# TMotor_Rev0_5_1_Jan30.net
KiCad netlist of a schematic drawn in EAGLE
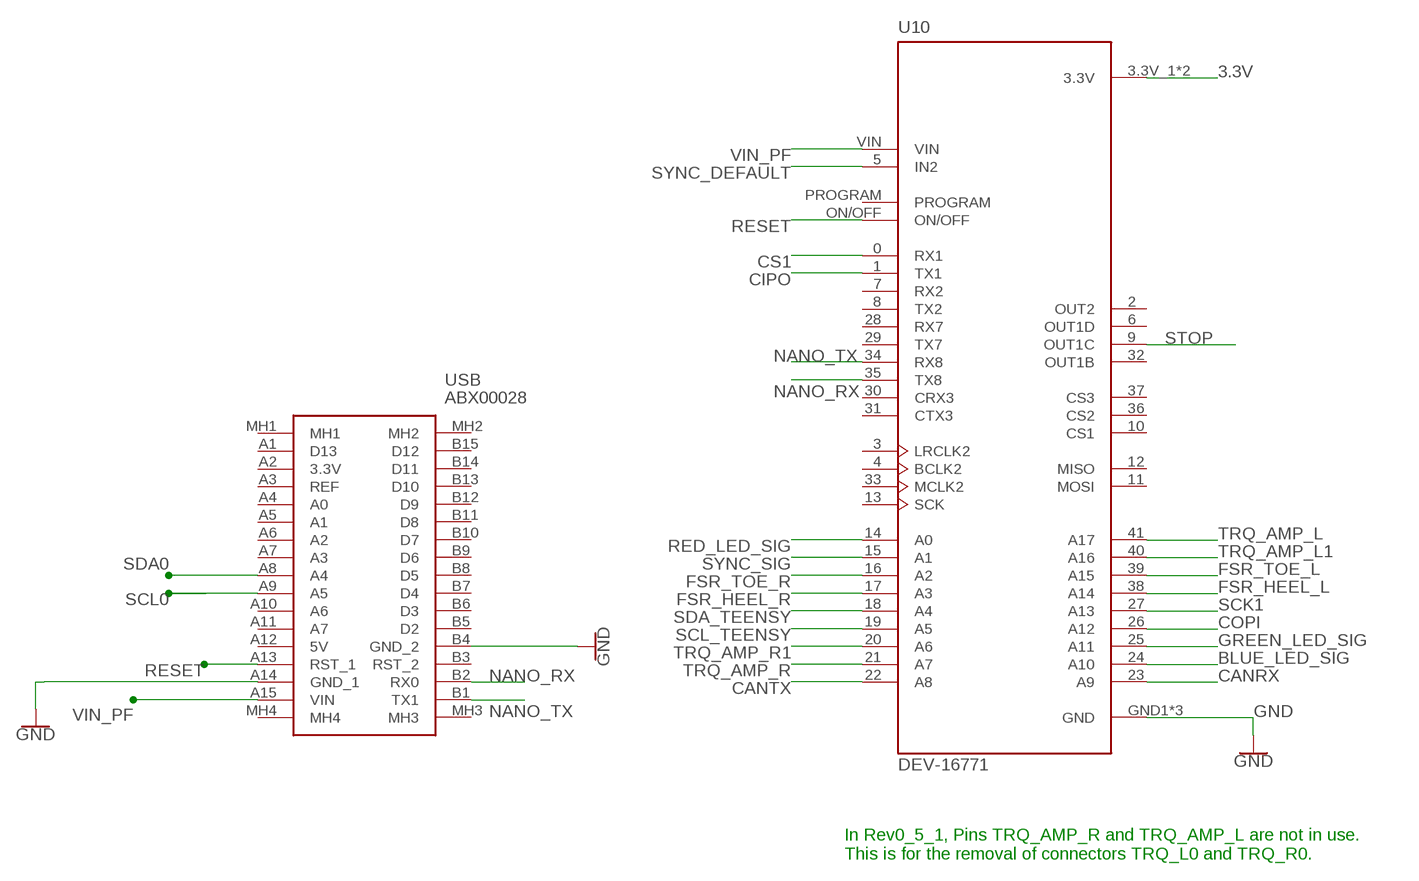
[diagram p0: schematic, sheet 1]
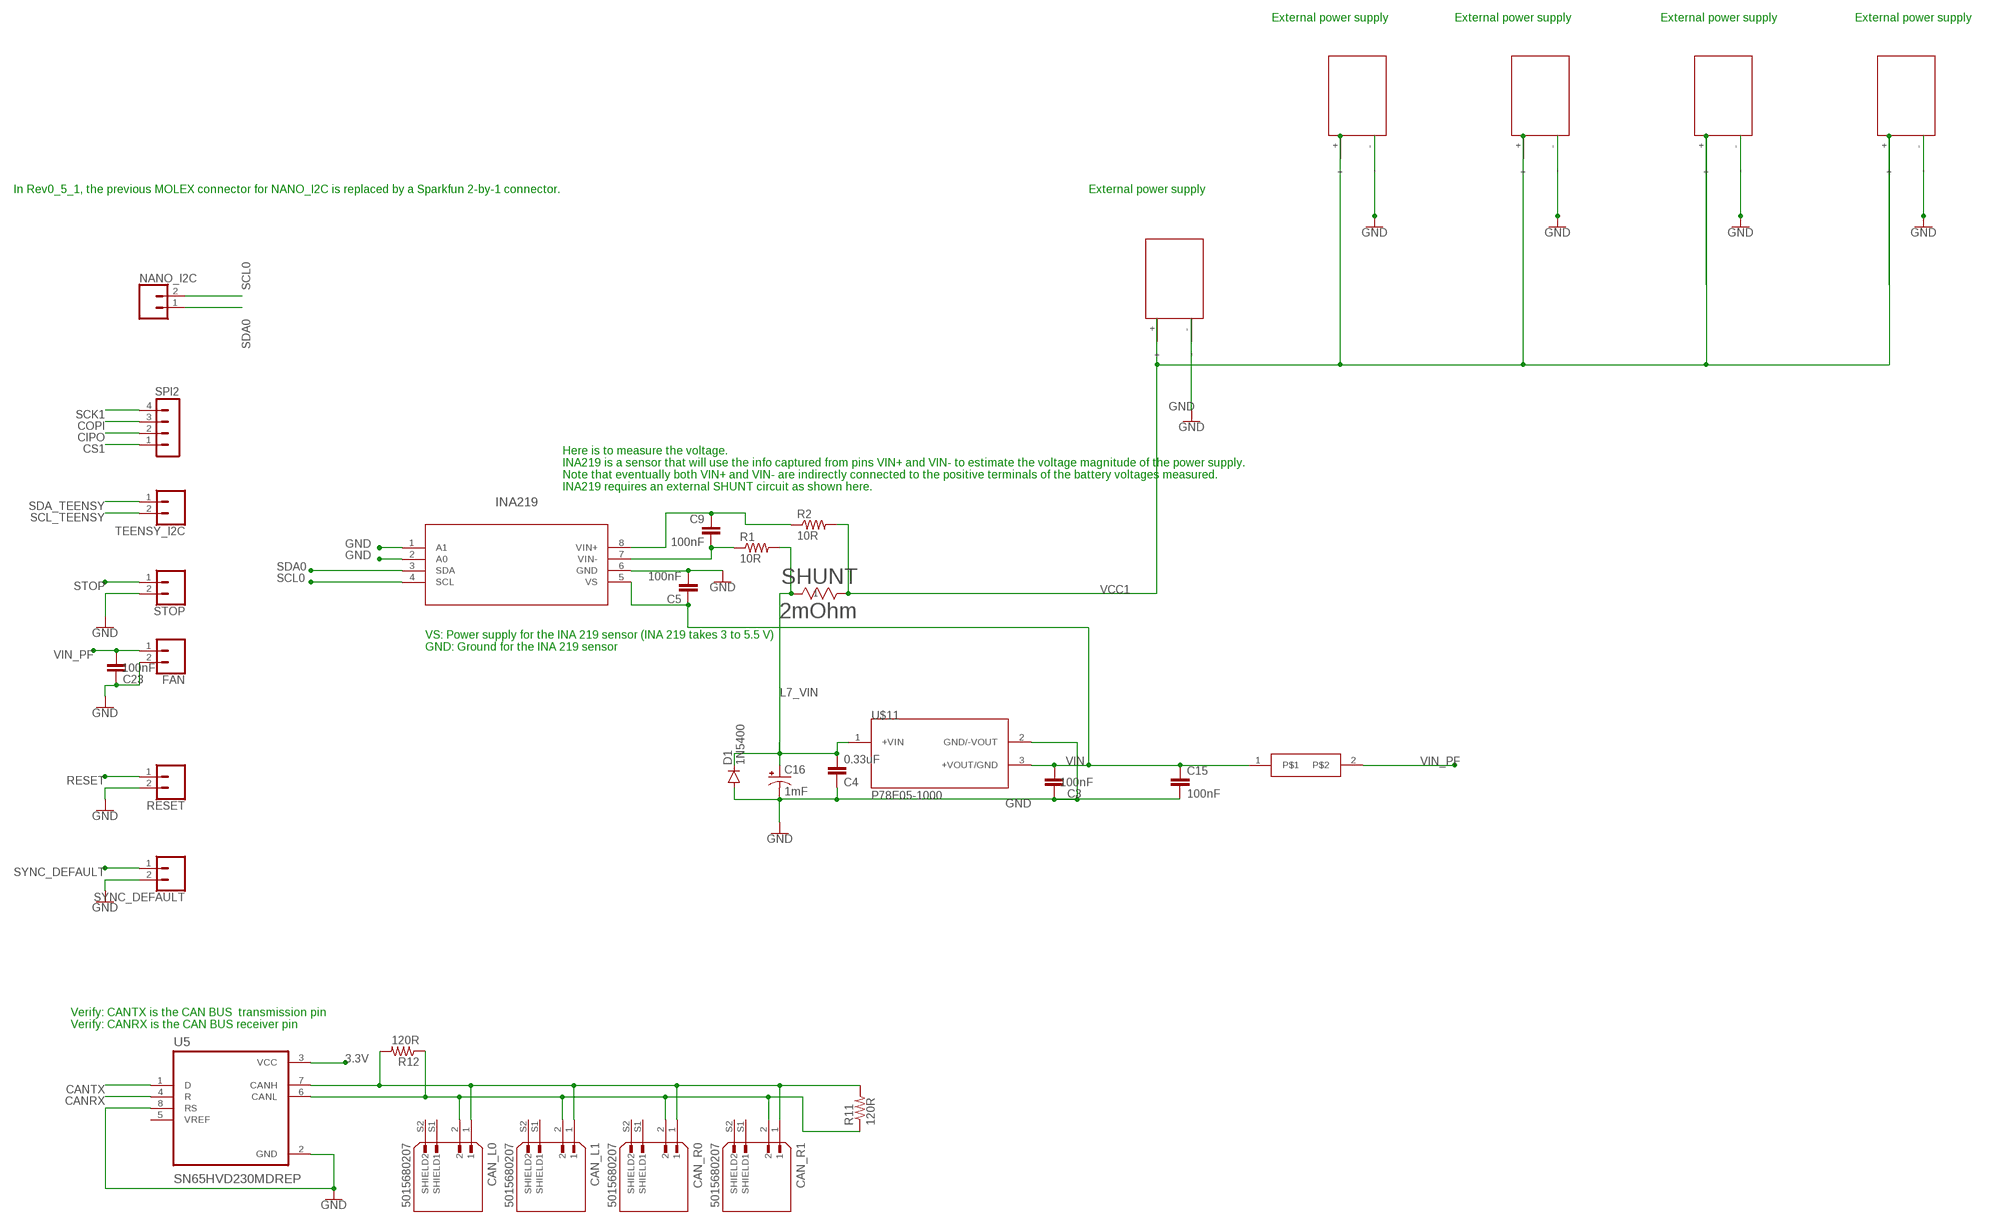
[diagram p1: schematic, sheet 2]
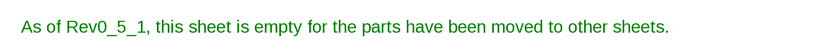
[diagram p2: schematic, sheet 3]
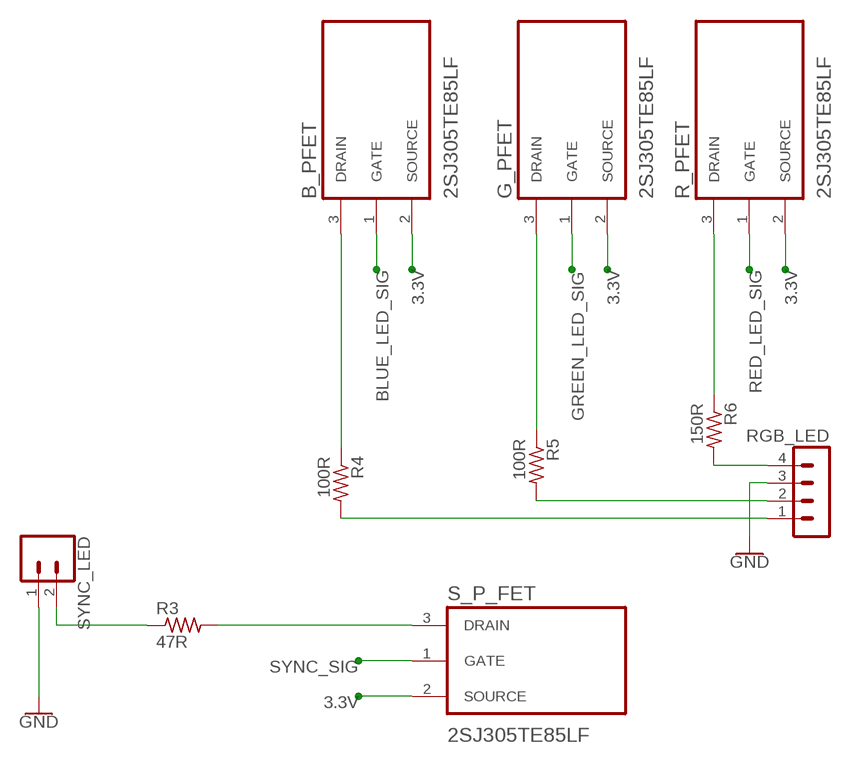
[diagram p3: schematic, sheet 4]
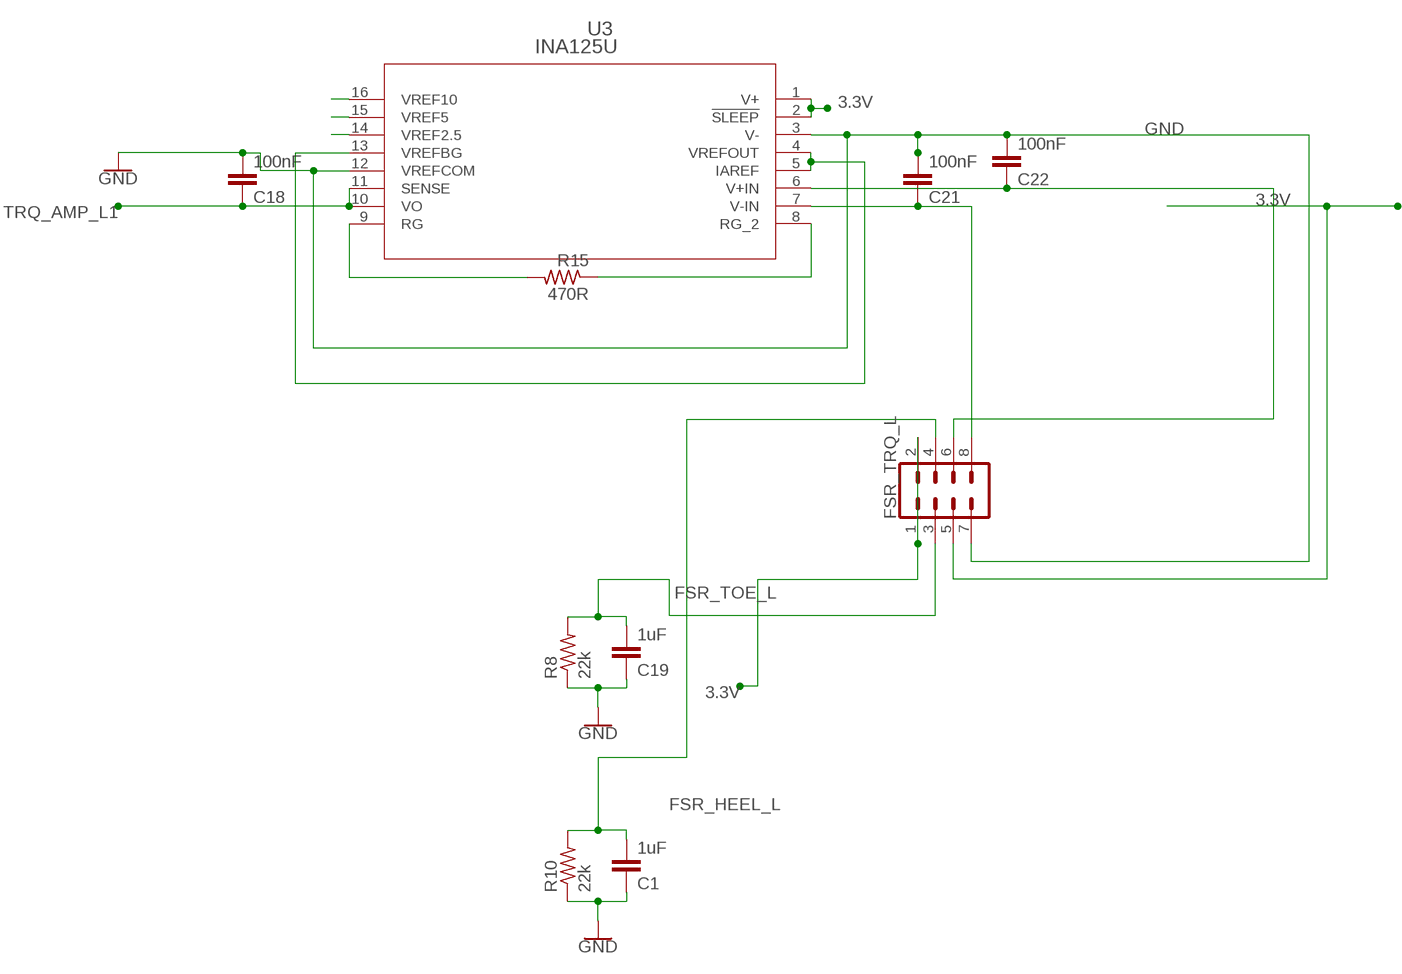
[diagram p4: schematic, sheet 5, part 1 of 2]
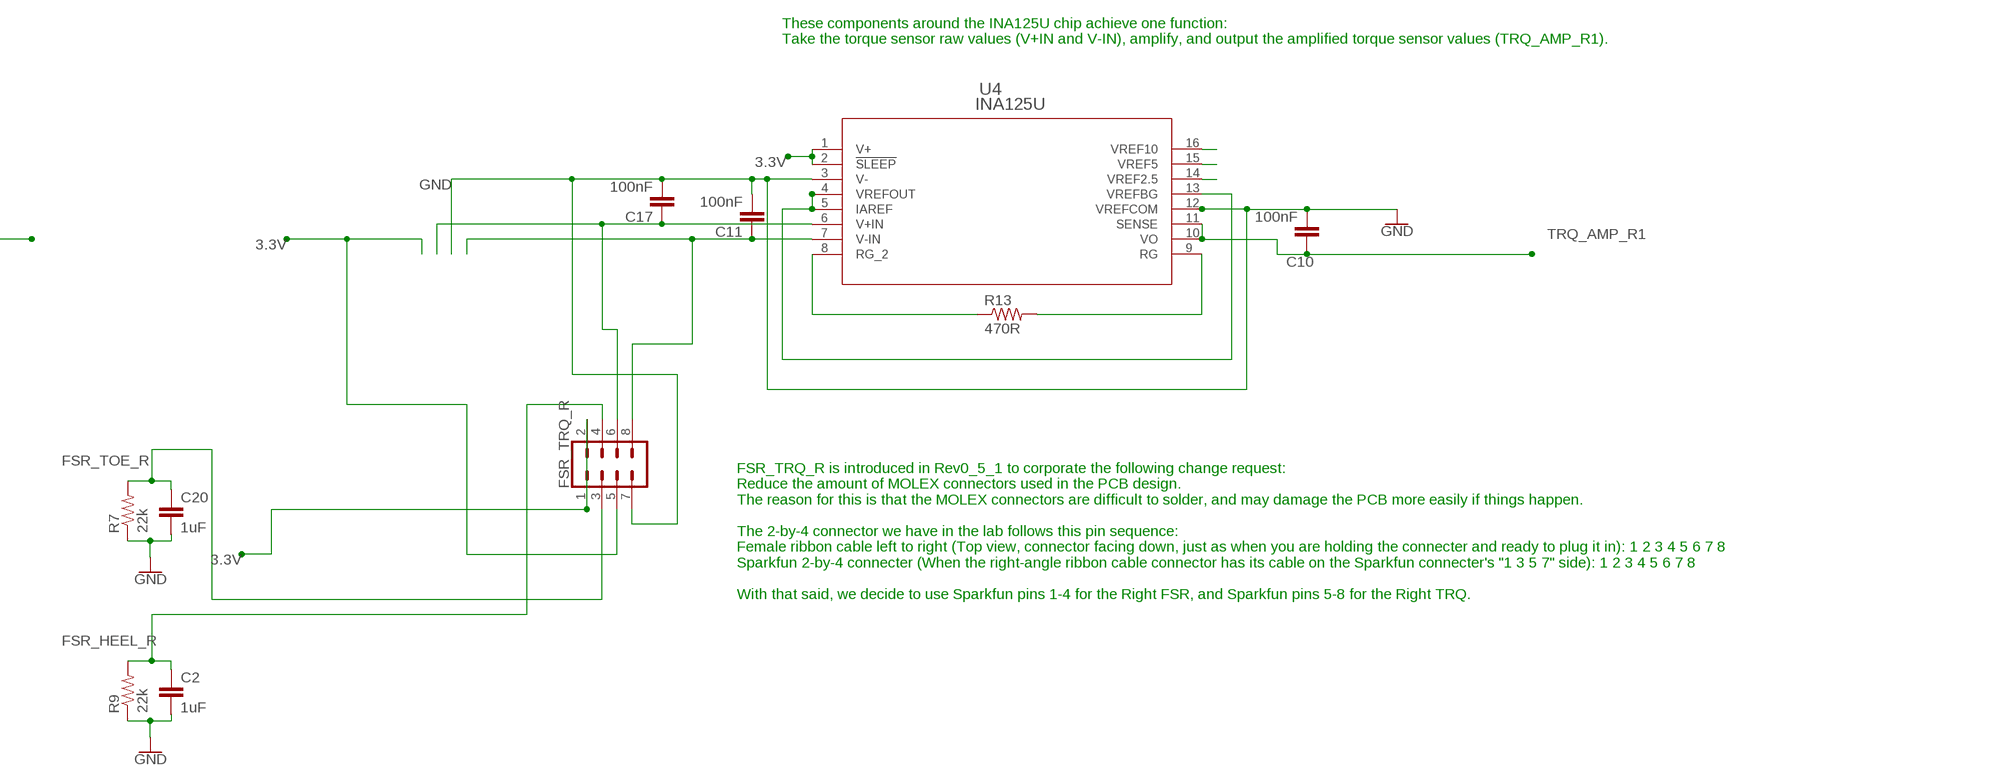
[diagram p5: schematic, sheet 5, part 2 of 2]

(export (version "E")
  (design (tool "Eeschema 10.0.6"))
  (components
    (comp (ref "C1")
      (value "1uF")
      (footprint "eagle-import:C050-024X044")
      (libsource (lib "eagle-import") (part "C-EU050-024X044"))
    )
    (comp (ref "C2")
      (value "1uF")
      (footprint "eagle-import:C050-024X044")
      (libsource (lib "eagle-import") (part "C-EU050-024X044"))
    )
    (comp (ref "C10")
      (value "100nF")
      (footprint "eagle-import:C050-024X044")
      (libsource (lib "eagle-import") (part "C-EU050-024X044"))
    )
    (comp (ref "C11")
      (value "100nF")
      (footprint "eagle-import:C050-024X044")
      (libsource (lib "eagle-import") (part "C-EU050-024X044"))
    )
    (comp (ref "C17")
      (value "100nF")
      (footprint "eagle-import:C050-024X044")
      (libsource (lib "eagle-import") (part "C-EU050-024X044"))
    )
    (comp (ref "C18")
      (value "100nF")
      (footprint "eagle-import:C050-024X044")
      (libsource (lib "eagle-import") (part "C-EU050-024X044"))
    )
    (comp (ref "C19")
      (value "1uF")
      (footprint "eagle-import:C050-024X044")
      (libsource (lib "eagle-import") (part "C-EU050-024X044"))
    )
    (comp (ref "C20")
      (value "1uF")
      (footprint "eagle-import:C050-024X044")
      (libsource (lib "eagle-import") (part "C-EU050-024X044"))
    )
    (comp (ref "C21")
      (value "100nF")
      (footprint "eagle-import:C050-024X044")
      (libsource (lib "eagle-import") (part "C-EU050-024X044"))
    )
    (comp (ref "C22")
      (value "100nF")
      (footprint "eagle-import:C050-024X044")
      (libsource (lib "eagle-import") (part "C-EU050-024X044"))
    )
    (comp (ref "FSR_TRQ_L")
      (value "CONN_04X2")
      (footprint "eagle-import:2X4")
      (libsource (lib "eagle-import") (part "CONN_04X2"))
    )
    (comp (ref "FSR_TRQ_R")
      (value "CONN_04X2")
      (footprint "eagle-import:2X4")
      (libsource (lib "eagle-import") (part "CONN_04X2"))
    )
    (comp (ref "R7")
      (value "22k")
      (footprint "eagle-import:0207_10")
      (libsource (lib "eagle-import") (part "resistor_348_R-US_0207/10"))
    )
    (comp (ref "R8")
      (value "22k")
      (footprint "eagle-import:0207_10")
      (libsource (lib "eagle-import") (part "resistor_348_R-US_0207/10"))
    )
    (comp (ref "R9")
      (value "22k")
      (footprint "eagle-import:0207_10")
      (libsource (lib "eagle-import") (part "resistor_348_R-US_0207/10"))
    )
    (comp (ref "R10")
      (value "22k")
      (footprint "eagle-import:0207_10")
      (libsource (lib "eagle-import") (part "resistor_348_R-US_0207/10"))
    )
    (comp (ref "R13")
      (value "470R")
      (footprint "eagle-import:0207_10")
      (libsource (lib "eagle-import") (part "R-US_0207/10"))
    )
    (comp (ref "R15")
      (value "470R")
      (footprint "eagle-import:0207_10")
      (libsource (lib "eagle-import") (part "R-US_0207/10"))
    )
    (comp (ref "U3")
      (value "INA125U")
      (footprint "eagle-import:D16")
      (fields (field (name "GENERIC_PART_NUMBER") "INA125") (field (name "MANUFACTURER") "Texas Instruments"))
      (libsource (lib "eagle-import") (part "INA125U"))
    )
    (comp (ref "U4")
      (value "INA125U")
      (footprint "eagle-import:D16")
      (fields (field (name "GENERIC_PART_NUMBER") "INA125") (field (name "MANUFACTURER") "Texas Instruments"))
      (libsource (lib "eagle-import") (part "INA125U"))
    )
    (comp (ref "B_PFET")
      (value "2SJ305TE85LF")
      (footprint "eagle-import:TRANS_SSM3J325F,LF")
      (fields (field (name "MF") "Toshiba"))
      (libsource (lib "eagle-import") (part "2SJ305TE85LF"))
    )
    (comp (ref "G_PFET")
      (value "2SJ305TE85LF")
      (footprint "eagle-import:TRANS_SSM3J325F,LF")
      (fields (field (name "MF") "Toshiba"))
      (libsource (lib "eagle-import") (part "2SJ305TE85LF"))
    )
    (comp (ref "R3")
      (value "47R")
      (footprint "eagle-import:0207_10")
      (libsource (lib "eagle-import") (part "R-US_0207/10"))
    )
    (comp (ref "R4")
      (value "100R")
      (footprint "eagle-import:0207_10")
      (libsource (lib "eagle-import") (part "R-US_0207/10"))
    )
    (comp (ref "R5")
      (value "100R")
      (footprint "eagle-import:0207_10")
      (libsource (lib "eagle-import") (part "R-US_0207/10"))
    )
    (comp (ref "R6")
      (value "150R")
      (footprint "eagle-import:0207_10")
      (libsource (lib "eagle-import") (part "R-US_0207/10"))
    )
    (comp (ref "RGB_LED")
      (value "MA04-1")
      (footprint "eagle-import:MA04-1")
      (libsource (lib "eagle-import") (part "MA04-1"))
    )
    (comp (ref "R_PFET")
      (value "2SJ305TE85LF")
      (footprint "eagle-import:TRANS_SSM3J325F,LF")
      (fields (field (name "MF") "Toshiba"))
      (libsource (lib "eagle-import") (part "2SJ305TE85LF"))
    )
    (comp (ref "SYNC_LED")
      (value "CONN_02")
      (footprint "eagle-import:1X02")
      (libsource (lib "eagle-import") (part "CONN_02"))
    )
    (comp (ref "S_P_FET")
      (value "2SJ305TE85LF")
      (footprint "eagle-import:TRANS_SSM3J325F,LF")
      (fields (field (name "MF") "Toshiba"))
      (libsource (lib "eagle-import") (part "2SJ305TE85LF"))
    )
    (comp (ref "U10")
      (value "DEV-16771")
      (footprint "eagle-import:MODULE_DEV-16771")
      (fields (field (name "MANUFACTURER") "SparkFun Electronics"))
      (libsource (lib "eagle-import") (part "DEV-16771"))
    )
    (comp (ref "USB")
      (value "ABX00028")
      (footprint "eagle-import:ABX00028")
      (fields (field (name "MOUSER_PART_NUMBER") "782-ABX00028"))
      (libsource (lib "eagle-import") (part "ABX00028"))
    )
    (comp (ref "C3")
      (value "100nF")
      (footprint "eagle-import:C050-024X044")
      (libsource (lib "eagle-import") (part "C-EU050-024X044"))
    )
    (comp (ref "C4")
      (value "0.33uF")
      (footprint "eagle-import:C050-024X044")
      (libsource (lib "eagle-import") (part "C-EU050-024X044"))
    )
    (comp (ref "C5")
      (value "100nF")
      (footprint "eagle-import:C050-024X044")
      (libsource (lib "eagle-import") (part "C-EU050-024X044"))
    )
    (comp (ref "C9")
      (value "100nF")
      (footprint "eagle-import:C050-024X044")
      (libsource (lib "eagle-import") (part "C-EU050-024X044"))
    )
    (comp (ref "C15")
      (value "100nF")
      (footprint "eagle-import:C050-024X044")
      (libsource (lib "eagle-import") (part "C-EU050-024X044"))
    )
    (comp (ref "C16")
      (value "1mF")
      (footprint "eagle-import:E5-10,5")
      (libsource (lib "eagle-import") (part "CPOL-USE5-10.5"))
    )
    (comp (ref "C23")
      (value "100nF")
      (footprint "eagle-import:C050-024X044")
      (libsource (lib "eagle-import") (part "C-EU050-024X044"))
    )
    (comp (ref "CAN_L0")
      (value "5015680207")
      (footprint "eagle-import:MOLEX_5015680207")
      (fields (field (name "MANUFACTURER") "Molex"))
      (libsource (lib "eagle-import") (part "5015680207"))
    )
    (comp (ref "CAN_L1")
      (value "5015680207")
      (footprint "eagle-import:MOLEX_5015680207")
      (fields (field (name "MANUFACTURER") "Molex"))
      (libsource (lib "eagle-import") (part "5015680207"))
    )
    (comp (ref "CAN_R0")
      (value "5015680207")
      (footprint "eagle-import:MOLEX_5015680207")
      (fields (field (name "MANUFACTURER") "Molex"))
      (libsource (lib "eagle-import") (part "5015680207"))
    )
    (comp (ref "CAN_R1")
      (value "5015680207")
      (footprint "eagle-import:MOLEX_5015680207")
      (fields (field (name "MANUFACTURER") "Molex"))
      (libsource (lib "eagle-import") (part "5015680207"))
    )
    (comp (ref "D1")
      (value "1N5400")
      (footprint "eagle-import:DO201-15")
      (libsource (lib "eagle-import") (part "1N5400"))
    )
    (comp (ref "FAN")
      (value "CONN_02")
      (footprint "eagle-import:1X02")
      (libsource (lib "eagle-import") (part "CONN_02"))
    )
    (comp (ref "INA219")
      (value "INA219AIDR")
      (footprint "eagle-import:D8_TEX")
      (libsource (lib "eagle-import") (part "INA219AIDR"))
    )
    (comp (ref "NANO_I2C")
      (value "CONN_02")
      (footprint "eagle-import:1X02")
      (libsource (lib "eagle-import") (part "CONN_02"))
    )
    (comp (ref "R1")
      (value "10R")
      (footprint "eagle-import:0207_10")
      (libsource (lib "eagle-import") (part "R-US_0207/10"))
    )
    (comp (ref "R2")
      (value "10R")
      (footprint "eagle-import:0207_10")
      (libsource (lib "eagle-import") (part "R-US_0207/10"))
    )
    (comp (ref "R11")
      (value "120R")
      (footprint "eagle-import:0207_10")
      (libsource (lib "eagle-import") (part "R-US_0207/10"))
    )
    (comp (ref "R12")
      (value "120R")
      (footprint "eagle-import:0207_10")
      (libsource (lib "eagle-import") (part "R-US_0207/10"))
    )
    (comp (ref "RESET")
      (value "CONN_02")
      (footprint "eagle-import:1X02")
      (libsource (lib "eagle-import") (part "CONN_02"))
    )
    (comp (ref "SHUNT")
      (value "2mOhm")
      (footprint "eagle-import:STA_CSNL2512(2)_STP")
      (fields (field (name "MANUFACTURER_PART_NUMBER") "CSNL2512FT2L00"))
      (libsource (lib "eagle-import") (part "CSNL2512FT2L00"))
    )
    (comp (ref "SPI2")
      (value "MA04-1")
      (footprint "eagle-import:MA04-1")
      (libsource (lib "eagle-import") (part "MA04-1"))
    )
    (comp (ref "STOP")
      (value "CONN_02")
      (footprint "eagle-import:1X02")
      (libsource (lib "eagle-import") (part "CONN_02"))
    )
    (comp (ref "SYNC_DEFAULT")
      (value "CONN_02")
      (footprint "eagle-import:1X02")
      (libsource (lib "eagle-import") (part "CONN_02"))
    )
    (comp (ref "TEENSY_I2C")
      (value "CONN_02")
      (footprint "eagle-import:1X02")
      (libsource (lib "eagle-import") (part "CONN_02"))
    )
    (comp (ref "U$6")
      (value "0458002.DR")
      (footprint "eagle-import:FUSE_LITTEL_448")
      (libsource (lib "eagle-import") (part "0458002.DR"))
    )
    (comp (ref "U$11")
      (value "P78E05-1000")
      (footprint "eagle-import:P78E05-1000")
      (libsource (lib "eagle-import") (part "P78E05-1000"))
    )
    (comp (ref "U5")
      (value "SN65HVD230MDREP")
      (footprint "eagle-import:SOIC127P599X175-8N")
      (libsource (lib "eagle-import") (part "SN65HVD230MDREP"))
    )
    (comp (ref "XT30UPB-F")
      (value "L_0")
      (footprint "eagle-import:XT30UPB-F")
      (libsource (lib "eagle-import") (part "XT30UPB-F"))
    )
    (comp (ref "XT30UPB-F1")
      (value "L_0")
      (footprint "eagle-import:XT30UPB-F")
      (libsource (lib "eagle-import") (part "XT30UPB-F"))
    )
    (comp (ref "XT30UPB-F2")
      (value "L_0")
      (footprint "eagle-import:XT30UPB-F")
      (libsource (lib "eagle-import") (part "XT30UPB-F"))
    )
    (comp (ref "XT30UPB-F3")
      (value "L_0")
      (footprint "eagle-import:XT30UPB-F")
      (libsource (lib "eagle-import") (part "XT30UPB-F"))
    )
    (comp (ref "XT30UPB-F4")
      (value "L_0")
      (footprint "eagle-import:XT30UPB-F")
      (libsource (lib "eagle-import") (part "XT30UPB-F"))
    )
  )
  (nets
    (net (code "1") (name "3.3V") (class "Default")
      (node (ref "B_PFET") (pin "2") (pinfunction "SOURCE_2") (pintype "bidirectional"))
      (node (ref "FSR_TRQ_L") (pin "1") (pinfunction "1_1") (pintype "passive"))
      (node (ref "FSR_TRQ_L") (pin "2") (pinfunction "2_2") (pintype "passive"))
      (node (ref "FSR_TRQ_L") (pin "5") (pinfunction "5_5") (pintype "passive"))
      (node (ref "FSR_TRQ_R") (pin "1") (pinfunction "1_1") (pintype "passive"))
      (node (ref "FSR_TRQ_R") (pin "2") (pinfunction "2_2") (pintype "passive"))
      (node (ref "FSR_TRQ_R") (pin "5") (pinfunction "5_5") (pintype "passive"))
      (node (ref "G_PFET") (pin "2") (pinfunction "SOURCE_2") (pintype "bidirectional"))
      (node (ref "R_PFET") (pin "2") (pinfunction "SOURCE_2") (pintype "bidirectional"))
      (node (ref "S_P_FET") (pin "2") (pinfunction "SOURCE_2") (pintype "bidirectional"))
      (node (ref "U10") (pin "3.3V_1") (pinfunction "3.3V_3.3V_1") (pintype "power_in"))
      (node (ref "U10") (pin "3.3V_2") (pinfunction "3.3V_3.3V_2") (pintype "power_in"))
      (node (ref "U3") (pin "1") (pinfunction "V+_1") (pintype "power_in"))
      (node (ref "U3") (pin "2") (pinfunction "~{SLEEP}_2") (pintype "passive"))
      (node (ref "U4") (pin "1") (pinfunction "V+_1") (pintype "power_in"))
      (node (ref "U4") (pin "2") (pinfunction "~{SLEEP}_2") (pintype "passive"))
      (node (ref "U5") (pin "3") (pinfunction "VCC_3") (pintype "power_in"))
    )
    (net (code "2") (name "BLUE_LED_SIG") (class "Default")
      (node (ref "B_PFET") (pin "1") (pinfunction "GATE_1") (pintype "bidirectional"))
      (node (ref "U10") (pin "24") (pinfunction "A10_24") (pintype "bidirectional"))
    )
    (net (code "3") (name "CANRX") (class "Default")
      (node (ref "U10") (pin "23") (pinfunction "A9_23") (pintype "bidirectional"))
      (node (ref "U5") (pin "4") (pinfunction "R_4") (pintype "input"))
    )
    (net (code "4") (name "CANTX") (class "Default")
      (node (ref "U10") (pin "22") (pinfunction "A8_22") (pintype "bidirectional"))
      (node (ref "U5") (pin "1") (pinfunction "D_1") (pintype "input"))
    )
    (net (code "5") (name "CIPO") (class "Default")
      (node (ref "SPI2") (pin "2") (pinfunction "2_2") (pintype "passive"))
      (node (ref "U10") (pin "1") (pinfunction "TX1_1") (pintype "bidirectional"))
    )
    (net (code "6") (name "COPI") (class "Default")
      (node (ref "SPI2") (pin "3") (pinfunction "3_3") (pintype "passive"))
      (node (ref "U10") (pin "26") (pinfunction "A12_26") (pintype "bidirectional"))
    )
    (net (code "7") (name "CS1") (class "Default")
      (node (ref "SPI2") (pin "1") (pinfunction "1_1") (pintype "passive"))
      (node (ref "U10") (pin "0") (pinfunction "RX1_0") (pintype "bidirectional"))
    )
    (net (code "8") (name "FSR_HEEL_L") (class "Default")
      (node (ref "C1") (pin "2") (pinfunction "2_2") (pintype "passive"))
      (node (ref "FSR_TRQ_L") (pin "4") (pinfunction "4_4") (pintype "passive"))
      (node (ref "R10") (pin "2") (pinfunction "2_2") (pintype "passive"))
      (node (ref "U10") (pin "38") (pinfunction "A14_38") (pintype "bidirectional"))
    )
    (net (code "9") (name "FSR_HEEL_R") (class "Default")
      (node (ref "C2") (pin "1") (pinfunction "1_1") (pintype "passive"))
      (node (ref "FSR_TRQ_R") (pin "4") (pinfunction "4_4") (pintype "passive"))
      (node (ref "R9") (pin "2") (pinfunction "2_2") (pintype "passive"))
      (node (ref "U10") (pin "17") (pinfunction "A3_17") (pintype "bidirectional"))
    )
    (net (code "10") (name "FSR_TOE_L") (class "Default")
      (node (ref "C19") (pin "2") (pinfunction "2_2") (pintype "passive"))
      (node (ref "FSR_TRQ_L") (pin "3") (pinfunction "3_3") (pintype "passive"))
      (node (ref "R8") (pin "2") (pinfunction "2_2") (pintype "passive"))
      (node (ref "U10") (pin "39") (pinfunction "A15_39") (pintype "bidirectional"))
    )
    (net (code "11") (name "FSR_TOE_R") (class "Default")
      (node (ref "C20") (pin "1") (pinfunction "1_1") (pintype "passive"))
      (node (ref "FSR_TRQ_R") (pin "3") (pinfunction "3_3") (pintype "passive"))
      (node (ref "R7") (pin "2") (pinfunction "2_2") (pintype "passive"))
      (node (ref "U10") (pin "16") (pinfunction "A2_16") (pintype "bidirectional"))
    )
    (net (code "12") (name "GND") (class "Default")
      (node (ref "C1") (pin "1") (pinfunction "1_1") (pintype "passive"))
      (node (ref "C10") (pin "2") (pinfunction "2_2") (pintype "passive"))
      (node (ref "C11") (pin "2") (pinfunction "2_2") (pintype "passive"))
      (node (ref "C15") (pin "2") (pinfunction "2_2") (pintype "passive"))
      (node (ref "C16") (pin "-") (pinfunction "-_-") (pintype "passive"))
      (node (ref "C17") (pin "2") (pinfunction "2_2") (pintype "passive"))
      (node (ref "C18") (pin "2") (pinfunction "2_2") (pintype "passive"))
      (node (ref "C19") (pin "1") (pinfunction "1_1") (pintype "passive"))
      (node (ref "C2") (pin "2") (pinfunction "2_2") (pintype "passive"))
      (node (ref "C20") (pin "2") (pinfunction "2_2") (pintype "passive"))
      (node (ref "C21") (pin "2") (pinfunction "2_2") (pintype "passive"))
      (node (ref "C22") (pin "2") (pinfunction "2_2") (pintype "passive"))
      (node (ref "C23") (pin "1") (pinfunction "1_1") (pintype "passive"))
      (node (ref "C3") (pin "1") (pinfunction "1_1") (pintype "passive"))
      (node (ref "C4") (pin "1") (pinfunction "1_1") (pintype "passive"))
      (node (ref "C5") (pin "2") (pinfunction "2_2") (pintype "passive"))
      (node (ref "D1") (pin "A") (pinfunction "A_A") (pintype "passive"))
      (node (ref "FAN") (pin "2") (pinfunction "2_2") (pintype "passive"))
      (node (ref "FSR_TRQ_L") (pin "7") (pinfunction "7_7") (pintype "passive"))
      (node (ref "FSR_TRQ_R") (pin "7") (pinfunction "7_7") (pintype "passive"))
      (node (ref "INA219") (pin "1") (pinfunction "A1_1") (pintype "passive"))
      (node (ref "INA219") (pin "2") (pinfunction "A0_2") (pintype "passive"))
      (node (ref "INA219") (pin "6") (pinfunction "GND_6") (pintype "power_in"))
      (node (ref "R10") (pin "1") (pinfunction "1_1") (pintype "passive"))
      (node (ref "R7") (pin "1") (pinfunction "1_1") (pintype "passive"))
      (node (ref "R8") (pin "1") (pinfunction "1_1") (pintype "passive"))
      (node (ref "R9") (pin "1") (pinfunction "1_1") (pintype "passive"))
      (node (ref "RESET") (pin "2") (pinfunction "2_2") (pintype "passive"))
      (node (ref "RGB_LED") (pin "3") (pinfunction "3_3") (pintype "passive"))
      (node (ref "STOP") (pin "2") (pinfunction "2_2") (pintype "passive"))
      (node (ref "SYNC_DEFAULT") (pin "2") (pinfunction "2_2") (pintype "passive"))
      (node (ref "SYNC_LED") (pin "1") (pinfunction "1_1") (pintype "passive"))
      (node (ref "U$11") (pin "2") (pinfunction "GND/-VOUT_2") (pintype "power_in"))
      (node (ref "U10") (pin "GND1") (pinfunction "GND_GND1") (pintype "power_in"))
      (node (ref "U10") (pin "GND2") (pinfunction "GND_GND2") (pintype "power_in"))
      (node (ref "U10") (pin "GND3") (pinfunction "GND_GND3") (pintype "power_in"))
      (node (ref "U3") (pin "12") (pinfunction "VREFCOM_12") (pintype "power_in"))
      (node (ref "U3") (pin "3") (pinfunction "V-_3") (pintype "power_in"))
      (node (ref "U4") (pin "12") (pinfunction "VREFCOM_12") (pintype "power_in"))
      (node (ref "U4") (pin "3") (pinfunction "V-_3") (pintype "power_in"))
      (node (ref "U5") (pin "2") (pinfunction "GND_2") (pintype "power_in"))
      (node (ref "U5") (pin "8") (pinfunction "RS_8") (pintype "input"))
      (node (ref "USB") (pin "A14") (pinfunction "GND_1_A14") (pintype "bidirectional"))
      (node (ref "USB") (pin "B4") (pinfunction "GND_2_B4") (pintype "bidirectional"))
      (node (ref "XT30UPB-F") (pin "-") (pinfunction "-_-") (pintype "output"))
      (node (ref "XT30UPB-F1") (pin "-") (pinfunction "-_-") (pintype "output"))
      (node (ref "XT30UPB-F2") (pin "-") (pinfunction "-_-") (pintype "output"))
      (node (ref "XT30UPB-F3") (pin "-") (pinfunction "-_-") (pintype "output"))
      (node (ref "XT30UPB-F4") (pin "-") (pinfunction "-_-") (pintype "output"))
    )
    (net (code "13") (name "GREEN_LED_SIG") (class "Default")
      (node (ref "G_PFET") (pin "1") (pinfunction "GATE_1") (pintype "bidirectional"))
      (node (ref "U10") (pin "25") (pinfunction "A11_25") (pintype "bidirectional"))
    )
    (net (code "14") (name "L7_VIN") (class "Default")
      (node (ref "C16") (pin "+") (pinfunction "+_+") (pintype "passive"))
      (node (ref "C4") (pin "2") (pinfunction "2_2") (pintype "passive"))
      (node (ref "D1") (pin "C") (pinfunction "C_C") (pintype "passive"))
      (node (ref "R1") (pin "2") (pinfunction "2_2") (pintype "passive"))
      (node (ref "SHUNT") (pin "1") (pinfunction "1_1") (pintype "passive"))
      (node (ref "U$11") (pin "1") (pinfunction "+VIN_1") (pintype "input"))
    )
    (net (code "15") (name "NANO_RX") (class "Default")
      (node (ref "U10") (pin "35") (pinfunction "TX8_35") (pintype "bidirectional"))
      (node (ref "USB") (pin "B2") (pinfunction "RX0_B2") (pintype "bidirectional"))
    )
    (net (code "16") (name "NANO_TX") (class "Default")
      (node (ref "U10") (pin "34") (pinfunction "RX8_34") (pintype "bidirectional"))
      (node (ref "USB") (pin "B1") (pinfunction "TX1_B1") (pintype "bidirectional"))
    )
    (net (code "17") (name "Net-(B_PFET-DRAIN)") (class "Default")
      (node (ref "B_PFET") (pin "3") (pinfunction "DRAIN_3") (pintype "input"))
      (node (ref "R4") (pin "1") (pinfunction "1_1") (pintype "passive"))
    )
    (net (code "18") (name "Net-(G_PFET-DRAIN)") (class "Default")
      (node (ref "G_PFET") (pin "3") (pinfunction "DRAIN_3") (pintype "input"))
      (node (ref "R5") (pin "1") (pinfunction "1_1") (pintype "passive"))
    )
    (net (code "19") (name "Net-(INA219-VIN+)") (class "Default")
      (node (ref "C9") (pin "1") (pinfunction "1_1") (pintype "passive"))
      (node (ref "INA219") (pin "8") (pinfunction "VIN+_8") (pintype "input"))
      (node (ref "R2") (pin "1") (pinfunction "1_1") (pintype "passive"))
    )
    (net (code "20") (name "Net-(INA219-VIN-)") (class "Default")
      (node (ref "C9") (pin "2") (pinfunction "2_2") (pintype "passive"))
      (node (ref "INA219") (pin "7") (pinfunction "VIN-_7") (pintype "input"))
      (node (ref "R1") (pin "1") (pinfunction "1_1") (pintype "passive"))
    )
    (net (code "21") (name "Net-(R3-Pad1)") (class "Default")
      (node (ref "R3") (pin "1") (pinfunction "1_1") (pintype "passive"))
      (node (ref "SYNC_LED") (pin "2") (pinfunction "2_2") (pintype "passive"))
    )
    (net (code "22") (name "Net-(R4-Pad2)") (class "Default")
      (node (ref "R4") (pin "2") (pinfunction "2_2") (pintype "passive"))
      (node (ref "RGB_LED") (pin "1") (pinfunction "1_1") (pintype "passive"))
    )
    (net (code "23") (name "Net-(R5-Pad2)") (class "Default")
      (node (ref "R5") (pin "2") (pinfunction "2_2") (pintype "passive"))
      (node (ref "RGB_LED") (pin "2") (pinfunction "2_2") (pintype "passive"))
    )
    (net (code "24") (name "Net-(R6-Pad2)") (class "Default")
      (node (ref "R6") (pin "2") (pinfunction "2_2") (pintype "passive"))
      (node (ref "RGB_LED") (pin "4") (pinfunction "4_4") (pintype "passive"))
    )
    (net (code "25") (name "Net-(R_PFET-DRAIN)") (class "Default")
      (node (ref "R6") (pin "1") (pinfunction "1_1") (pintype "passive"))
      (node (ref "R_PFET") (pin "3") (pinfunction "DRAIN_3") (pintype "input"))
    )
    (net (code "26") (name "Net-(S_P_FET-DRAIN)") (class "Default")
      (node (ref "R3") (pin "2") (pinfunction "2_2") (pintype "passive"))
      (node (ref "S_P_FET") (pin "3") (pinfunction "DRAIN_3") (pintype "input"))
    )
    (net (code "27") (name "Net-(U3-IAREF)") (class "Default")
      (node (ref "U3") (pin "13") (pinfunction "VREFBG_13") (pintype "power_in"))
      (node (ref "U3") (pin "4") (pinfunction "VREFOUT_4") (pintype "output"))
      (node (ref "U3") (pin "5") (pinfunction "IAREF_5") (pintype "passive"))
    )
    (net (code "28") (name "Net-(U3-RG)") (class "Default")
      (node (ref "R15") (pin "2") (pinfunction "2_2") (pintype "passive"))
      (node (ref "U3") (pin "9") (pinfunction "RG_9") (pintype "passive"))
    )
    (net (code "29") (name "Net-(U3-RG_2)") (class "Default")
      (node (ref "R15") (pin "1") (pinfunction "1_1") (pintype "passive"))
      (node (ref "U3") (pin "8") (pinfunction "RG_2_8") (pintype "passive"))
    )
    (net (code "30") (name "Net-(U3-V+IN)") (class "Default")
      (node (ref "C22") (pin "1") (pinfunction "1_1") (pintype "passive"))
      (node (ref "FSR_TRQ_L") (pin "6") (pinfunction "6_6") (pintype "passive"))
      (node (ref "U3") (pin "6") (pinfunction "V+IN_6") (pintype "input"))
    )
    (net (code "31") (name "Net-(U3-V-IN)") (class "Default")
      (node (ref "C21") (pin "1") (pinfunction "1_1") (pintype "passive"))
      (node (ref "FSR_TRQ_L") (pin "8") (pinfunction "8_8") (pintype "passive"))
      (node (ref "U3") (pin "7") (pinfunction "V-IN_7") (pintype "input"))
    )
    (net (code "32") (name "Net-(U4-IAREF)") (class "Default")
      (node (ref "U4") (pin "13") (pinfunction "VREFBG_13") (pintype "power_in"))
      (node (ref "U4") (pin "4") (pinfunction "VREFOUT_4") (pintype "output"))
      (node (ref "U4") (pin "5") (pinfunction "IAREF_5") (pintype "passive"))
    )
    (net (code "33") (name "Net-(U4-RG)") (class "Default")
      (node (ref "R13") (pin "2") (pinfunction "2_2") (pintype "passive"))
      (node (ref "U4") (pin "9") (pinfunction "RG_9") (pintype "passive"))
    )
    (net (code "34") (name "Net-(U4-RG_2)") (class "Default")
      (node (ref "R13") (pin "1") (pinfunction "1_1") (pintype "passive"))
      (node (ref "U4") (pin "8") (pinfunction "RG_2_8") (pintype "passive"))
    )
    (net (code "35") (name "Net-(U4-V+IN)") (class "Default")
      (node (ref "C17") (pin "1") (pinfunction "1_1") (pintype "passive"))
      (node (ref "FSR_TRQ_R") (pin "6") (pinfunction "6_6") (pintype "passive"))
      (node (ref "U4") (pin "6") (pinfunction "V+IN_6") (pintype "input"))
    )
    (net (code "36") (name "Net-(U4-V-IN)") (class "Default")
      (node (ref "C11") (pin "1") (pinfunction "1_1") (pintype "passive"))
      (node (ref "FSR_TRQ_R") (pin "8") (pinfunction "8_8") (pintype "passive"))
      (node (ref "U4") (pin "7") (pinfunction "V-IN_7") (pintype "input"))
    )
    (net (code "37") (name "Net-(U5-CANH)") (class "Default")
      (node (ref "CAN_L0") (pin "1") (pinfunction "1_1") (pintype "passive"))
      (node (ref "CAN_L1") (pin "1") (pinfunction "1_1") (pintype "passive"))
      (node (ref "CAN_R0") (pin "1") (pinfunction "1_1") (pintype "passive"))
      (node (ref "CAN_R1") (pin "1") (pinfunction "1_1") (pintype "passive"))
      (node (ref "R11") (pin "2") (pinfunction "2_2") (pintype "passive"))
      (node (ref "R12") (pin "2") (pinfunction "2_2") (pintype "passive"))
      (node (ref "U5") (pin "7") (pinfunction "CANH_7") (pintype "output"))
    )
    (net (code "38") (name "Net-(U5-CANL)") (class "Default")
      (node (ref "CAN_L0") (pin "2") (pinfunction "2_2") (pintype "passive"))
      (node (ref "CAN_L1") (pin "2") (pinfunction "2_2") (pintype "passive"))
      (node (ref "CAN_R0") (pin "2") (pinfunction "2_2") (pintype "passive"))
      (node (ref "CAN_R1") (pin "2") (pinfunction "2_2") (pintype "passive"))
      (node (ref "R11") (pin "1") (pinfunction "1_1") (pintype "passive"))
      (node (ref "R12") (pin "1") (pinfunction "1_1") (pintype "passive"))
      (node (ref "U5") (pin "6") (pinfunction "CANL_6") (pintype "output"))
    )
    (net (code "39") (name "RED_LED_SIG") (class "Default")
      (node (ref "R_PFET") (pin "1") (pinfunction "GATE_1") (pintype "bidirectional"))
      (node (ref "U10") (pin "14") (pinfunction "A0_14") (pintype "bidirectional"))
    )
    (net (code "40") (name "RESET") (class "Default")
      (node (ref "RESET") (pin "1") (pinfunction "1_1") (pintype "passive"))
      (node (ref "U10") (pin "ON/OFF") (pinfunction "ON/OFF_ON/OFF") (pintype "bidirectional"))
      (node (ref "USB") (pin "A13") (pinfunction "RST_1_A13") (pintype "bidirectional"))
    )
    (net (code "41") (name "SCK1") (class "Default")
      (node (ref "SPI2") (pin "4") (pinfunction "4_4") (pintype "passive"))
      (node (ref "U10") (pin "27") (pinfunction "A13_27") (pintype "bidirectional"))
    )
    (net (code "42") (name "SCL0") (class "Default")
      (node (ref "INA219") (pin "4") (pinfunction "SCL_4") (pintype "passive"))
      (node (ref "NANO_I2C") (pin "2") (pinfunction "2_2") (pintype "passive"))
      (node (ref "USB") (pin "A9") (pinfunction "A5_A9") (pintype "bidirectional"))
    )
    (net (code "43") (name "SCL_TEENSY") (class "Default")
      (node (ref "TEENSY_I2C") (pin "2") (pinfunction "2_2") (pintype "passive"))
      (node (ref "U10") (pin "19") (pinfunction "A5_19") (pintype "bidirectional"))
    )
    (net (code "44") (name "SDA0") (class "Default")
      (node (ref "INA219") (pin "3") (pinfunction "SDA_3") (pintype "passive"))
      (node (ref "NANO_I2C") (pin "1") (pinfunction "1_1") (pintype "passive"))
      (node (ref "USB") (pin "A8") (pinfunction "A4_A8") (pintype "bidirectional"))
    )
    (net (code "45") (name "SDA_TEENSY") (class "Default")
      (node (ref "TEENSY_I2C") (pin "1") (pinfunction "1_1") (pintype "passive"))
      (node (ref "U10") (pin "18") (pinfunction "A4_18") (pintype "bidirectional"))
    )
    (net (code "46") (name "STOP") (class "Default")
      (node (ref "STOP") (pin "1") (pinfunction "1_1") (pintype "passive"))
      (node (ref "U10") (pin "9") (pinfunction "OUT1C_9") (pintype "output"))
    )
    (net (code "47") (name "SYNC_DEFAULT") (class "Default")
      (node (ref "SYNC_DEFAULT") (pin "1") (pinfunction "1_1") (pintype "passive"))
      (node (ref "U10") (pin "5") (pinfunction "IN2_5") (pintype "bidirectional"))
    )
    (net (code "48") (name "SYNC_SIG") (class "Default")
      (node (ref "S_P_FET") (pin "1") (pinfunction "GATE_1") (pintype "bidirectional"))
      (node (ref "U10") (pin "15") (pinfunction "A1_15") (pintype "bidirectional"))
    )
    (net (code "49") (name "TRQ_AMP_L") (class "Default")
      (node (ref "U10") (pin "41") (pinfunction "A17_41") (pintype "bidirectional"))
    )
    (net (code "50") (name "TRQ_AMP_L1") (class "Default")
      (node (ref "C18") (pin "1") (pinfunction "1_1") (pintype "passive"))
      (node (ref "U10") (pin "40") (pinfunction "A16_40") (pintype "bidirectional"))
      (node (ref "U3") (pin "10") (pinfunction "VO_10") (pintype "output"))
      (node (ref "U3") (pin "11") (pinfunction "SENSE_11") (pintype "passive"))
    )
    (net (code "51") (name "TRQ_AMP_R") (class "Default")
      (node (ref "U10") (pin "21") (pinfunction "A7_21") (pintype "bidirectional"))
    )
    (net (code "52") (name "TRQ_AMP_R1") (class "Default")
      (node (ref "C10") (pin "1") (pinfunction "1_1") (pintype "passive"))
      (node (ref "U10") (pin "20") (pinfunction "A6_20") (pintype "bidirectional"))
      (node (ref "U4") (pin "10") (pinfunction "VO_10") (pintype "output"))
      (node (ref "U4") (pin "11") (pinfunction "SENSE_11") (pintype "passive"))
    )
    (net (code "53") (name "VCC1") (class "Default")
      (node (ref "R2") (pin "2") (pinfunction "2_2") (pintype "passive"))
      (node (ref "SHUNT") (pin "2") (pinfunction "2_2") (pintype "passive"))
      (node (ref "XT30UPB-F") (pin "+") (pinfunction "+_+") (pintype "output"))
      (node (ref "XT30UPB-F1") (pin "+") (pinfunction "+_+") (pintype "output"))
      (node (ref "XT30UPB-F2") (pin "+") (pinfunction "+_+") (pintype "output"))
      (node (ref "XT30UPB-F3") (pin "+") (pinfunction "+_+") (pintype "output"))
      (node (ref "XT30UPB-F4") (pin "+") (pinfunction "+_+") (pintype "output"))
    )
    (net (code "54") (name "VIN") (class "Default")
      (node (ref "C15") (pin "1") (pinfunction "1_1") (pintype "passive"))
      (node (ref "C3") (pin "2") (pinfunction "2_2") (pintype "passive"))
      (node (ref "C5") (pin "1") (pinfunction "1_1") (pintype "passive"))
      (node (ref "INA219") (pin "5") (pinfunction "VS_5") (pintype "power_in"))
      (node (ref "U$11") (pin "3") (pinfunction "+VOUT/GND_3") (pintype "power_in"))
      (node (ref "U$6") (pin "1") (pinfunction "P$1_1") (pintype "bidirectional"))
    )
    (net (code "55") (name "VIN_PF") (class "Default")
      (node (ref "C23") (pin "2") (pinfunction "2_2") (pintype "passive"))
      (node (ref "FAN") (pin "1") (pinfunction "1_1") (pintype "passive"))
      (node (ref "U$6") (pin "2") (pinfunction "P$2_2") (pintype "bidirectional"))
      (node (ref "U10") (pin "VIN") (pinfunction "VIN_VIN") (pintype "input"))
      (node (ref "USB") (pin "A15") (pinfunction "VIN_A15") (pintype "bidirectional"))
    )
    (net (code "56") (name "unconnected-(CAN_L0-SHIELD1-PadS1)") (class "Default")
      (node (ref "CAN_L0") (pin "S1") (pinfunction "SHIELD1_S1") (pintype "passive"))
    )
    (net (code "57") (name "unconnected-(CAN_L0-SHIELD2-PadS2)") (class "Default")
      (node (ref "CAN_L0") (pin "S2") (pinfunction "SHIELD2_S2") (pintype "passive"))
    )
    (net (code "58") (name "unconnected-(CAN_L1-SHIELD1-PadS1)") (class "Default")
      (node (ref "CAN_L1") (pin "S1") (pinfunction "SHIELD1_S1") (pintype "passive"))
    )
    (net (code "59") (name "unconnected-(CAN_L1-SHIELD2-PadS2)") (class "Default")
      (node (ref "CAN_L1") (pin "S2") (pinfunction "SHIELD2_S2") (pintype "passive"))
    )
    (net (code "60") (name "unconnected-(CAN_R0-SHIELD1-PadS1)") (class "Default")
      (node (ref "CAN_R0") (pin "S1") (pinfunction "SHIELD1_S1") (pintype "passive"))
    )
    (net (code "61") (name "unconnected-(CAN_R0-SHIELD2-PadS2)") (class "Default")
      (node (ref "CAN_R0") (pin "S2") (pinfunction "SHIELD2_S2") (pintype "passive"))
    )
    (net (code "62") (name "unconnected-(CAN_R1-SHIELD1-PadS1)") (class "Default")
      (node (ref "CAN_R1") (pin "S1") (pinfunction "SHIELD1_S1") (pintype "passive"))
    )
    (net (code "63") (name "unconnected-(CAN_R1-SHIELD2-PadS2)") (class "Default")
      (node (ref "CAN_R1") (pin "S2") (pinfunction "SHIELD2_S2") (pintype "passive"))
    )
    (net (code "64") (name "unconnected-(U3-VREF2.5-Pad14)") (class "Default")
      (node (ref "U3") (pin "14") (pinfunction "VREF2.5_14") (pintype "power_in"))
    )
    (net (code "65") (name "unconnected-(U3-VREF5-Pad15)") (class "Default")
      (node (ref "U3") (pin "15") (pinfunction "VREF5_15") (pintype "power_in"))
    )
    (net (code "66") (name "unconnected-(U3-VREF10-Pad16)") (class "Default")
      (node (ref "U3") (pin "16") (pinfunction "VREF10_16") (pintype "power_in"))
    )
    (net (code "67") (name "unconnected-(U4-VREF2.5-Pad14)") (class "Default")
      (node (ref "U4") (pin "14") (pinfunction "VREF2.5_14") (pintype "power_in"))
    )
    (net (code "68") (name "unconnected-(U4-VREF5-Pad15)") (class "Default")
      (node (ref "U4") (pin "15") (pinfunction "VREF5_15") (pintype "power_in"))
    )
    (net (code "69") (name "unconnected-(U4-VREF10-Pad16)") (class "Default")
      (node (ref "U4") (pin "16") (pinfunction "VREF10_16") (pintype "power_in"))
    )
    (net (code "70") (name "unconnected-(U5-VREF-Pad5)") (class "Default")
      (node (ref "U5") (pin "5") (pinfunction "VREF_5") (pintype "input"))
    )
    (net (code "71") (name "unconnected-(U10-BCLK2-Pad4)") (class "Default")
      (node (ref "U10") (pin "4") (pinfunction "BCLK2_4") (pintype "bidirectional"))
    )
    (net (code "72") (name "unconnected-(U10-CRX3-Pad30)") (class "Default")
      (node (ref "U10") (pin "30") (pinfunction "CRX3_30") (pintype "bidirectional"))
    )
    (net (code "73") (name "unconnected-(U10-CS1-Pad10)") (class "Default")
      (node (ref "U10") (pin "10") (pinfunction "CS1_10") (pintype "bidirectional"))
    )
    (net (code "74") (name "unconnected-(U10-CS2-Pad36)") (class "Default")
      (node (ref "U10") (pin "36") (pinfunction "CS2_36") (pintype "bidirectional"))
    )
    (net (code "75") (name "unconnected-(U10-CS3-Pad37)") (class "Default")
      (node (ref "U10") (pin "37") (pinfunction "CS3_37") (pintype "bidirectional"))
    )
    (net (code "76") (name "unconnected-(U10-CTX3-Pad31)") (class "Default")
      (node (ref "U10") (pin "31") (pinfunction "CTX3_31") (pintype "bidirectional"))
    )
    (net (code "77") (name "unconnected-(U10-LRCLK2-Pad3)") (class "Default")
      (node (ref "U10") (pin "3") (pinfunction "LRCLK2_3") (pintype "bidirectional"))
    )
    (net (code "78") (name "unconnected-(U10-MCLK2-Pad33)") (class "Default")
      (node (ref "U10") (pin "33") (pinfunction "MCLK2_33") (pintype "bidirectional"))
    )
    (net (code "79") (name "unconnected-(U10-MISO-Pad12)") (class "Default")
      (node (ref "U10") (pin "12") (pinfunction "MISO_12") (pintype "bidirectional"))
    )
    (net (code "80") (name "unconnected-(U10-MOSI-Pad11)") (class "Default")
      (node (ref "U10") (pin "11") (pinfunction "MOSI_11") (pintype "bidirectional"))
    )
    (net (code "81") (name "unconnected-(U10-OUT1B-Pad32)") (class "Default")
      (node (ref "U10") (pin "32") (pinfunction "OUT1B_32") (pintype "output"))
    )
    (net (code "82") (name "unconnected-(U10-OUT1D-Pad6)") (class "Default")
      (node (ref "U10") (pin "6") (pinfunction "OUT1D_6") (pintype "output"))
    )
    (net (code "83") (name "unconnected-(U10-OUT2-Pad2)") (class "Default")
      (node (ref "U10") (pin "2") (pinfunction "OUT2_2") (pintype "output"))
    )
    (net (code "84") (name "unconnected-(U10-PadPROGRAM)") (class "Default")
      (node (ref "U10") (pin "PROGRAM") (pinfunction "PROGRAM_PROGRAM") (pintype "bidirectional"))
    )
    (net (code "85") (name "unconnected-(U10-RX2-Pad7)") (class "Default")
      (node (ref "U10") (pin "7") (pinfunction "RX2_7") (pintype "bidirectional"))
    )
    (net (code "86") (name "unconnected-(U10-RX7-Pad28)") (class "Default")
      (node (ref "U10") (pin "28") (pinfunction "RX7_28") (pintype "bidirectional"))
    )
    (net (code "87") (name "unconnected-(U10-SCK-Pad13)") (class "Default")
      (node (ref "U10") (pin "13") (pinfunction "SCK_13") (pintype "bidirectional"))
    )
    (net (code "88") (name "unconnected-(U10-TX2-Pad8)") (class "Default")
      (node (ref "U10") (pin "8") (pinfunction "TX2_8") (pintype "bidirectional"))
    )
    (net (code "89") (name "unconnected-(U10-TX7-Pad29)") (class "Default")
      (node (ref "U10") (pin "29") (pinfunction "TX7_29") (pintype "bidirectional"))
    )
    (net (code "90") (name "unconnected-(USB-3.3V-PadA2)") (class "Default")
      (node (ref "USB") (pin "A2") (pinfunction "3.3V_A2") (pintype "bidirectional"))
    )
    (net (code "91") (name "unconnected-(USB-5V-PadA12)") (class "Default")
      (node (ref "USB") (pin "A12") (pinfunction "5V_A12") (pintype "bidirectional"))
    )
    (net (code "92") (name "unconnected-(USB-A0-PadA4)") (class "Default")
      (node (ref "USB") (pin "A4") (pinfunction "A0_A4") (pintype "bidirectional"))
    )
    (net (code "93") (name "unconnected-(USB-A1-PadA5)") (class "Default")
      (node (ref "USB") (pin "A5") (pinfunction "A1_A5") (pintype "bidirectional"))
    )
    (net (code "94") (name "unconnected-(USB-A2-PadA6)") (class "Default")
      (node (ref "USB") (pin "A6") (pinfunction "A2_A6") (pintype "bidirectional"))
    )
    (net (code "95") (name "unconnected-(USB-A3-PadA7)") (class "Default")
      (node (ref "USB") (pin "A7") (pinfunction "A3_A7") (pintype "bidirectional"))
    )
    (net (code "96") (name "unconnected-(USB-A6-PadA10)") (class "Default")
      (node (ref "USB") (pin "A10") (pinfunction "A6_A10") (pintype "bidirectional"))
    )
    (net (code "97") (name "unconnected-(USB-A7-PadA11)") (class "Default")
      (node (ref "USB") (pin "A11") (pinfunction "A7_A11") (pintype "bidirectional"))
    )
    (net (code "98") (name "unconnected-(USB-D2-PadB5)") (class "Default")
      (node (ref "USB") (pin "B5") (pinfunction "D2_B5") (pintype "bidirectional"))
    )
    (net (code "99") (name "unconnected-(USB-D3-PadB6)") (class "Default")
      (node (ref "USB") (pin "B6") (pinfunction "D3_B6") (pintype "bidirectional"))
    )
    (net (code "100") (name "unconnected-(USB-D4-PadB7)") (class "Default")
      (node (ref "USB") (pin "B7") (pinfunction "D4_B7") (pintype "bidirectional"))
    )
    (net (code "101") (name "unconnected-(USB-D5-PadB8)") (class "Default")
      (node (ref "USB") (pin "B8") (pinfunction "D5_B8") (pintype "bidirectional"))
    )
    (net (code "102") (name "unconnected-(USB-D6-PadB9)") (class "Default")
      (node (ref "USB") (pin "B9") (pinfunction "D6_B9") (pintype "bidirectional"))
    )
    (net (code "103") (name "unconnected-(USB-D7-PadB10)") (class "Default")
      (node (ref "USB") (pin "B10") (pinfunction "D7_B10") (pintype "bidirectional"))
    )
    (net (code "104") (name "unconnected-(USB-D8-PadB11)") (class "Default")
      (node (ref "USB") (pin "B11") (pinfunction "D8_B11") (pintype "bidirectional"))
    )
    (net (code "105") (name "unconnected-(USB-D9-PadB12)") (class "Default")
      (node (ref "USB") (pin "B12") (pinfunction "D9_B12") (pintype "bidirectional"))
    )
    (net (code "106") (name "unconnected-(USB-D10-PadB13)") (class "Default")
      (node (ref "USB") (pin "B13") (pinfunction "D10_B13") (pintype "bidirectional"))
    )
    (net (code "107") (name "unconnected-(USB-D11-PadB14)") (class "Default")
      (node (ref "USB") (pin "B14") (pinfunction "D11_B14") (pintype "bidirectional"))
    )
    (net (code "108") (name "unconnected-(USB-D12-PadB15)") (class "Default")
      (node (ref "USB") (pin "B15") (pinfunction "D12_B15") (pintype "bidirectional"))
    )
    (net (code "109") (name "unconnected-(USB-D13-PadA1)") (class "Default")
      (node (ref "USB") (pin "A1") (pinfunction "D13_A1") (pintype "bidirectional"))
    )
    (net (code "110") (name "unconnected-(USB-PadMH1)") (class "Default")
      (node (ref "USB") (pin "MH1") (pinfunction "MH1_MH1") (pintype "bidirectional"))
    )
    (net (code "111") (name "unconnected-(USB-PadMH2)") (class "Default")
      (node (ref "USB") (pin "MH2") (pinfunction "MH2_MH2") (pintype "bidirectional"))
    )
    (net (code "112") (name "unconnected-(USB-PadMH3)") (class "Default")
      (node (ref "USB") (pin "MH3") (pinfunction "MH3_MH3") (pintype "bidirectional"))
    )
    (net (code "113") (name "unconnected-(USB-PadMH4)") (class "Default")
      (node (ref "USB") (pin "MH4") (pinfunction "MH4_MH4") (pintype "bidirectional"))
    )
    (net (code "114") (name "unconnected-(USB-REF-PadA3)") (class "Default")
      (node (ref "USB") (pin "A3") (pinfunction "REF_A3") (pintype "bidirectional"))
    )
    (net (code "115") (name "unconnected-(USB-RST_2-PadB3)") (class "Default")
      (node (ref "USB") (pin "B3") (pinfunction "RST_2_B3") (pintype "bidirectional"))
    )
  )
)
